# FPGA_System_Monitor.net
KiCad netlist of a schematic drawn in Altium Designer
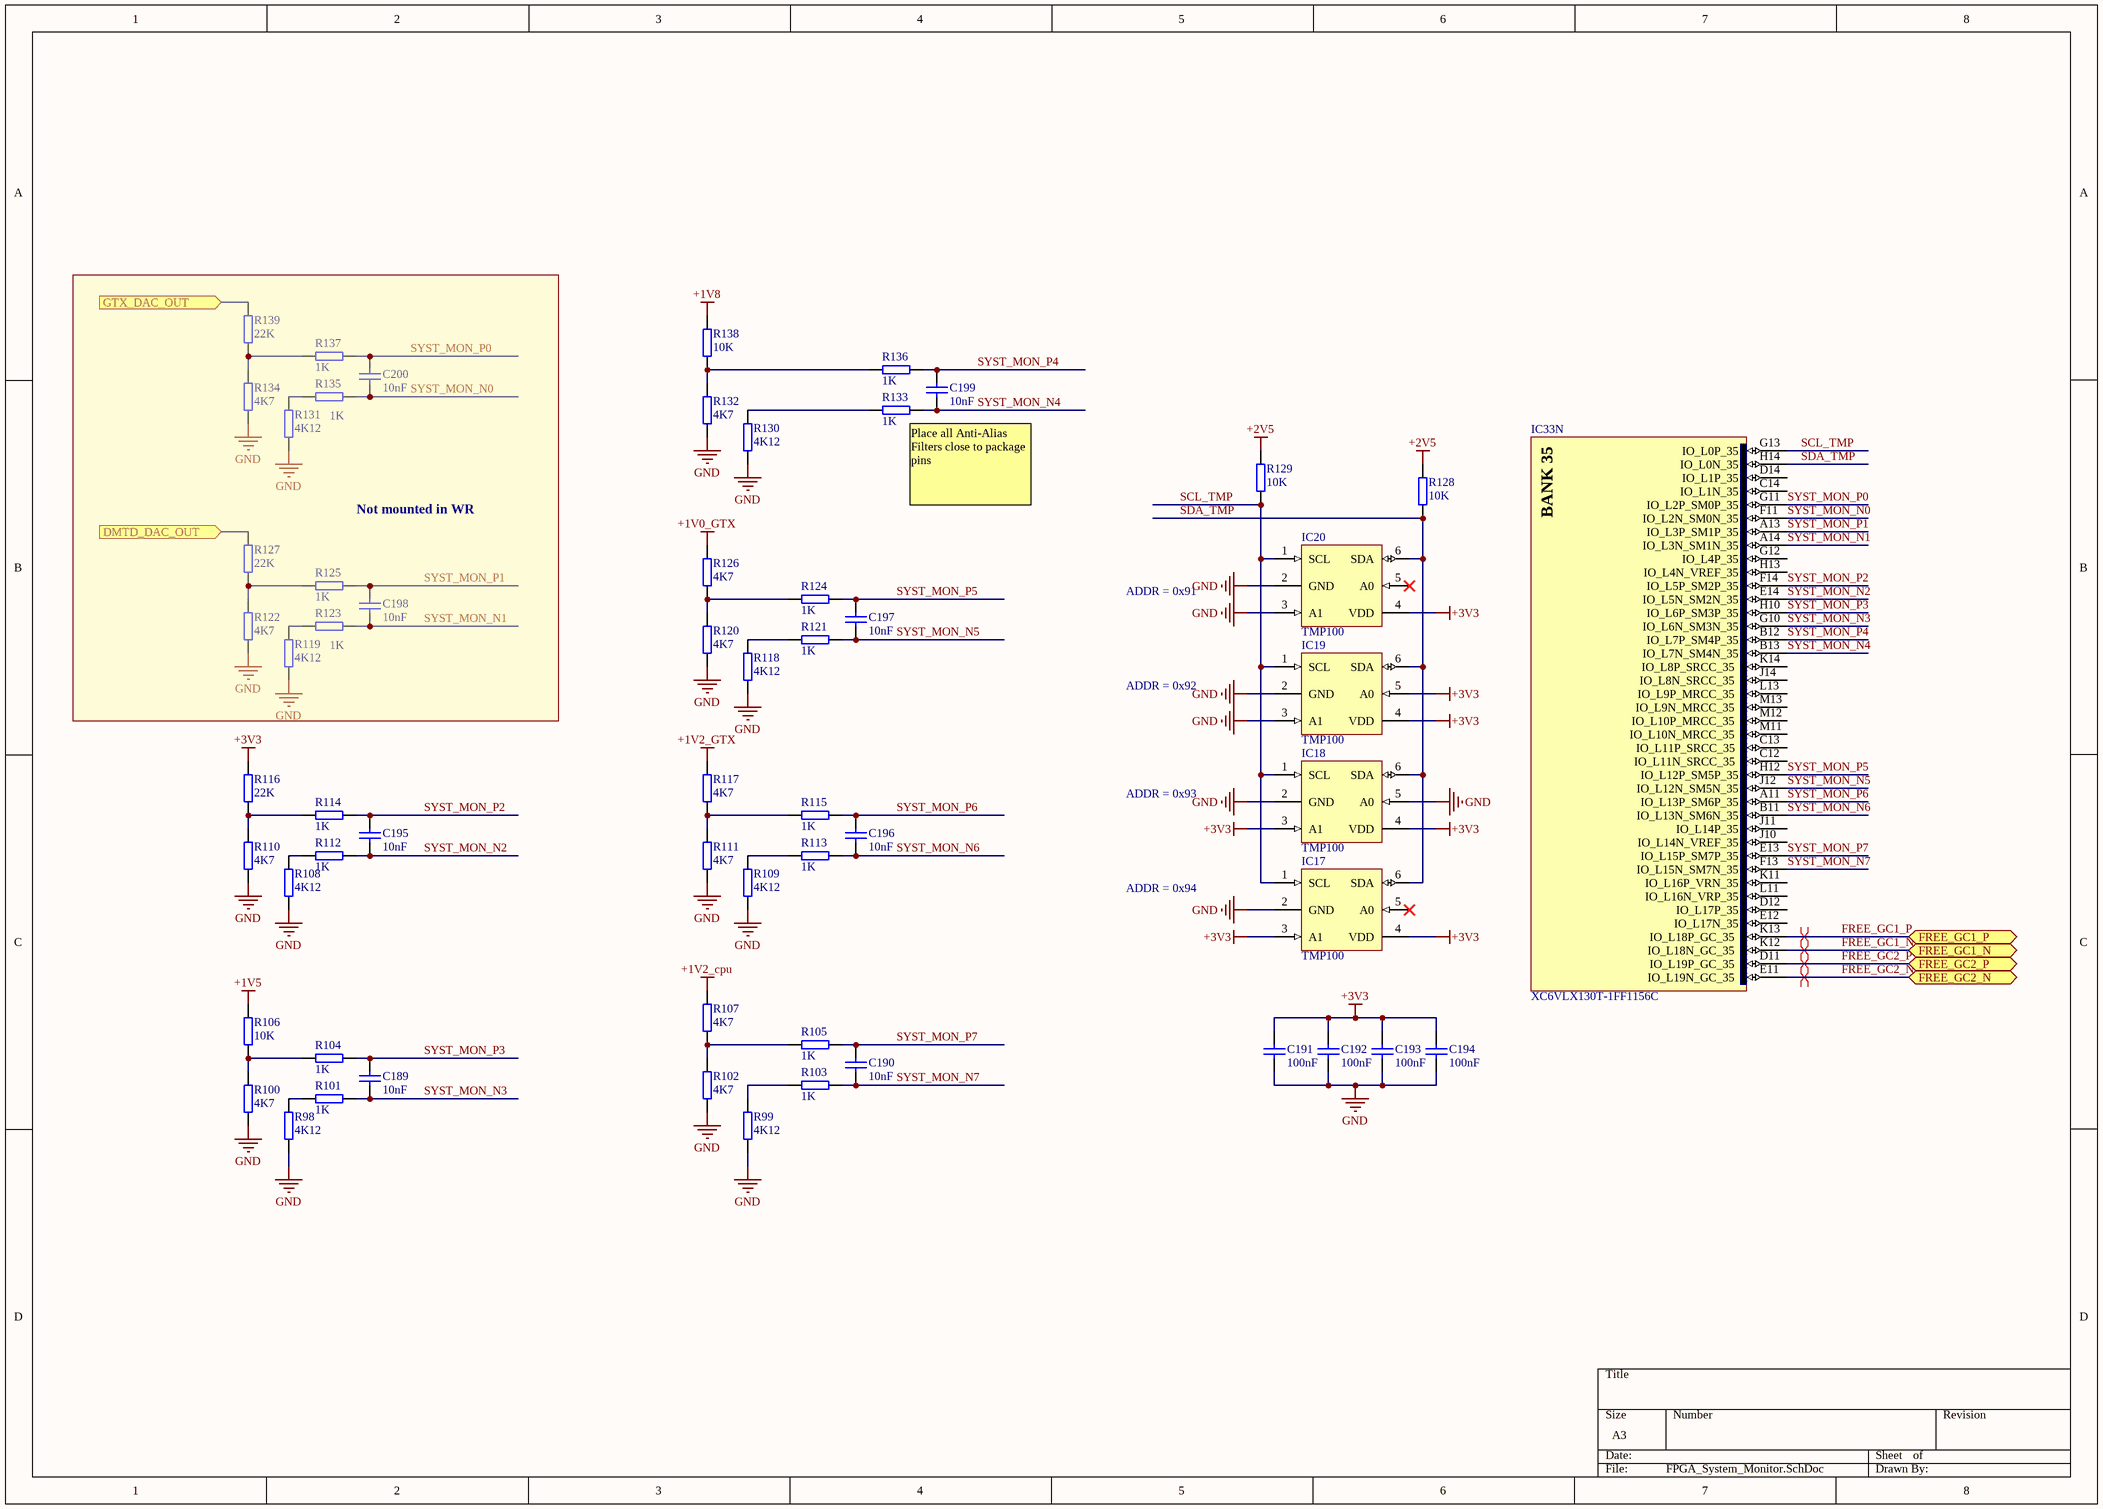
[diagram p0: FPGA_System_Monitor.SchDoc]

(export (version "E")
  (design (tool "Eeschema 10.0.6"))
  (components
    (comp (ref "C189")
      (value "10nF")
      (footprint "CC1005-0402")
      (description "Capacitor")
      (fields
        (field (name "TOLERANCE") "±10%")
        (field (name "VOLTAGE") "25V")
        (field (name "PUBLISHER") "Altium Limited")
      )
      (libsource (lib "wr_switch") (part "Cap"))
    )
    (comp (ref "C190")
      (value "10nF")
      (footprint "CC1005-0402")
      (description "Capacitor")
      (fields
        (field (name "TOLERANCE") "±10%")
        (field (name "VOLTAGE") "25V")
        (field (name "PUBLISHER") "Altium Limited")
      )
      (libsource (lib "wr_switch") (part "Cap"))
    )
    (comp (ref "C191")
      (value "100nF")
      (footprint "CC1005-0402")
      (description "Capacitor")
      (fields
        (field (name "TOLERANCE") "±10%")
        (field (name "VOLTAGE") "16V")
        (field (name "PUBLISHER") "Altium Limited")
      )
      (libsource (lib "wr_switch") (part "Cap"))
    )
    (comp (ref "C192")
      (value "100nF")
      (footprint "CC1005-0402")
      (description "Capacitor")
      (fields
        (field (name "TOLERANCE") "±10%")
        (field (name "VOLTAGE") "16V")
        (field (name "PUBLISHER") "Altium Limited")
      )
      (libsource (lib "wr_switch") (part "Cap"))
    )
    (comp (ref "C193")
      (value "100nF")
      (footprint "CC1005-0402")
      (description "Capacitor")
      (fields
        (field (name "TOLERANCE") "±10%")
        (field (name "VOLTAGE") "16V")
        (field (name "PUBLISHER") "Altium Limited")
      )
      (libsource (lib "wr_switch") (part "Cap"))
    )
    (comp (ref "C194")
      (value "100nF")
      (footprint "CC1005-0402")
      (description "Capacitor")
      (fields
        (field (name "TOLERANCE") "±10%")
        (field (name "VOLTAGE") "16V")
        (field (name "PUBLISHER") "Altium Limited")
      )
      (libsource (lib "wr_switch") (part "Cap"))
    )
    (comp (ref "C195")
      (value "10nF")
      (footprint "CC1005-0402")
      (description "Capacitor")
      (fields
        (field (name "TOLERANCE") "±10%")
        (field (name "VOLTAGE") "25V")
        (field (name "PUBLISHER") "Altium Limited")
      )
      (libsource (lib "wr_switch") (part "Cap"))
    )
    (comp (ref "C196")
      (value "10nF")
      (footprint "CC1005-0402")
      (description "Capacitor")
      (fields
        (field (name "TOLERANCE") "±10%")
        (field (name "VOLTAGE") "25V")
        (field (name "PUBLISHER") "Altium Limited")
      )
      (libsource (lib "wr_switch") (part "Cap"))
    )
    (comp (ref "C197")
      (value "10nF")
      (footprint "CC1005-0402")
      (description "Capacitor")
      (fields
        (field (name "TOLERANCE") "±10%")
        (field (name "VOLTAGE") "25V")
        (field (name "PUBLISHER") "Altium Limited")
      )
      (libsource (lib "wr_switch") (part "Cap"))
    )
    (comp (ref "C198")
      (value "10nF")
      (footprint "CC1005-0402")
      (description "Capacitor")
      (fields
        (field (name "TOLERANCE") "±10%")
        (field (name "VOLTAGE") "25V")
        (field (name "PUBLISHER") "Altium Limited")
      )
      (libsource (lib "wr_switch") (part "Cap"))
    )
    (comp (ref "C199")
      (value "10nF")
      (footprint "CC1005-0402")
      (description "Capacitor")
      (fields
        (field (name "TOLERANCE") "±10%")
        (field (name "VOLTAGE") "25V")
        (field (name "PUBLISHER") "Altium Limited")
      )
      (libsource (lib "wr_switch") (part "Cap"))
    )
    (comp (ref "C200")
      (value "10nF")
      (footprint "CC1005-0402")
      (description "Capacitor")
      (fields
        (field (name "TOLERANCE") "±10%")
        (field (name "VOLTAGE") "25V")
        (field (name "PUBLISHER") "Altium Limited")
      )
      (libsource (lib "wr_switch") (part "Cap"))
    )
    (comp (ref "IC17")
      (value "TMP100")
      (footprint "SOT23A-6L")
      (description "I2C temp. sensor")
      (libsource (lib "wr_switch") (part "TMP100"))
    )
    (comp (ref "IC18")
      (value "TMP100")
      (footprint "SOT23A-6L")
      (description "I2C temp. sensor")
      (libsource (lib "wr_switch") (part "TMP100"))
    )
    (comp (ref "IC19")
      (value "TMP100")
      (footprint "SOT23A-6L")
      (description "I2C temp. sensor")
      (libsource (lib "wr_switch") (part "TMP100"))
    )
    (comp (ref "IC20")
      (value "TMP100")
      (footprint "SOT23A-6L")
      (description "I2C temp. sensor")
      (libsource (lib "wr_switch") (part "TMP100"))
    )
    (comp (ref "IC33")
      (value "XC6VLX130T-1FF1156C")
      (footprint "FF1156")
      (fields (field (name "PUBLISHER") "Altium Limited"))
      (libsource (lib "Xilinx Virtex-6") (part "XC6VLX130T-1FF1156C"))
    )
    (comp (ref "R98")
      (value "4K12")
      (footprint "0402")
      (description "SMD Resistor")
      (fields (field (name "TOLERANCE") "±1%"))
      (libsource (lib "wr_switch") (part "RES_SMD"))
    )
    (comp (ref "R99")
      (value "4K12")
      (footprint "0402")
      (description "SMD Resistor")
      (fields (field (name "TOLERANCE") "±1%"))
      (libsource (lib "wr_switch") (part "RES_SMD"))
    )
    (comp (ref "R100")
      (value "4K7")
      (footprint "0402")
      (description "SMD Resistor")
      (fields (field (name "TOLERANCE") "±1%"))
      (libsource (lib "wr_switch") (part "RES_SMD"))
    )
    (comp (ref "R101")
      (value "1K")
      (footprint "0402")
      (description "SMD Resistor")
      (fields (field (name "TOLERANCE") "±1%"))
      (libsource (lib "wr_switch") (part "RES_SMD"))
    )
    (comp (ref "R102")
      (value "4K7")
      (footprint "0402")
      (description "SMD Resistor")
      (fields (field (name "TOLERANCE") "±1%"))
      (libsource (lib "wr_switch") (part "RES_SMD"))
    )
    (comp (ref "R103")
      (value "1K")
      (footprint "0402")
      (description "SMD Resistor")
      (fields (field (name "TOLERANCE") "±1%"))
      (libsource (lib "wr_switch") (part "RES_SMD"))
    )
    (comp (ref "R104")
      (value "1K")
      (footprint "0402")
      (description "SMD Resistor")
      (fields (field (name "TOLERANCE") "±1%"))
      (libsource (lib "wr_switch") (part "RES_SMD"))
    )
    (comp (ref "R105")
      (value "1K")
      (footprint "0402")
      (description "SMD Resistor")
      (fields (field (name "TOLERANCE") "±1%"))
      (libsource (lib "wr_switch") (part "RES_SMD"))
    )
    (comp (ref "R106")
      (value "10K")
      (footprint "0402")
      (description "SMD Resistor")
      (fields (field (name "TOLERANCE") "±1%") (field (name "Comment") "10k"))
      (libsource (lib "wr_switch") (part "RES_SMD"))
    )
    (comp (ref "R107")
      (value "4K7")
      (footprint "0402")
      (description "SMD Resistor")
      (fields (field (name "TOLERANCE") "±1%"))
      (libsource (lib "wr_switch") (part "RES_SMD"))
    )
    (comp (ref "R108")
      (value "4K12")
      (footprint "0402")
      (description "SMD Resistor")
      (fields (field (name "TOLERANCE") "±1%"))
      (libsource (lib "wr_switch") (part "RES_SMD"))
    )
    (comp (ref "R109")
      (value "4K12")
      (footprint "0402")
      (description "SMD Resistor")
      (fields (field (name "TOLERANCE") "±1%"))
      (libsource (lib "wr_switch") (part "RES_SMD"))
    )
    (comp (ref "R110")
      (value "4K7")
      (footprint "0402")
      (description "SMD Resistor")
      (fields (field (name "TOLERANCE") "±1%"))
      (libsource (lib "wr_switch") (part "RES_SMD"))
    )
    (comp (ref "R111")
      (value "4K7")
      (footprint "0402")
      (description "SMD Resistor")
      (fields (field (name "TOLERANCE") "±1%"))
      (libsource (lib "wr_switch") (part "RES_SMD"))
    )
    (comp (ref "R112")
      (value "1K")
      (footprint "0402")
      (description "SMD Resistor")
      (fields (field (name "TOLERANCE") "±1%"))
      (libsource (lib "wr_switch") (part "RES_SMD"))
    )
    (comp (ref "R113")
      (value "1K")
      (footprint "0402")
      (description "SMD Resistor")
      (fields (field (name "TOLERANCE") "±1%"))
      (libsource (lib "wr_switch") (part "RES_SMD"))
    )
    (comp (ref "R114")
      (value "1K")
      (footprint "0402")
      (description "SMD Resistor")
      (fields (field (name "TOLERANCE") "±1%"))
      (libsource (lib "wr_switch") (part "RES_SMD"))
    )
    (comp (ref "R115")
      (value "1K")
      (footprint "0402")
      (description "SMD Resistor")
      (fields (field (name "TOLERANCE") "±1%"))
      (libsource (lib "wr_switch") (part "RES_SMD"))
    )
    (comp (ref "R116")
      (value "22K")
      (footprint "0402")
      (description "SMD Resistor")
      (fields (field (name "TOLERANCE") "±1%"))
      (libsource (lib "wr_switch") (part "RES_SMD"))
    )
    (comp (ref "R117")
      (value "4K7")
      (footprint "0402")
      (description "SMD Resistor")
      (fields (field (name "TOLERANCE") "±1%"))
      (libsource (lib "wr_switch") (part "RES_SMD"))
    )
    (comp (ref "R118")
      (value "4K12")
      (footprint "0402")
      (description "SMD Resistor")
      (fields (field (name "TOLERANCE") "±1%"))
      (libsource (lib "wr_switch") (part "RES_SMD"))
    )
    (comp (ref "R119")
      (value "4K12")
      (footprint "0402")
      (description "SMD Resistor")
      (fields (field (name "TOLERANCE") "±1%"))
      (libsource (lib "wr_switch") (part "RES_SMD"))
    )
    (comp (ref "R120")
      (value "4K7")
      (footprint "0402")
      (description "SMD Resistor")
      (fields (field (name "TOLERANCE") "±1%"))
      (libsource (lib "wr_switch") (part "RES_SMD"))
    )
    (comp (ref "R121")
      (value "1K")
      (footprint "0402")
      (description "SMD Resistor")
      (fields (field (name "TOLERANCE") "±1%"))
      (libsource (lib "wr_switch") (part "RES_SMD"))
    )
    (comp (ref "R122")
      (value "4K7")
      (footprint "0402")
      (description "SMD Resistor")
      (fields (field (name "TOLERANCE") "±1%"))
      (libsource (lib "wr_switch") (part "RES_SMD"))
    )
    (comp (ref "R123")
      (value "1K")
      (footprint "0402")
      (description "SMD Resistor")
      (fields (field (name "TOLERANCE") "±1%"))
      (libsource (lib "wr_switch") (part "RES_SMD"))
    )
    (comp (ref "R124")
      (value "1K")
      (footprint "0402")
      (description "SMD Resistor")
      (fields (field (name "TOLERANCE") "±1%"))
      (libsource (lib "wr_switch") (part "RES_SMD"))
    )
    (comp (ref "R125")
      (value "1K")
      (footprint "0402")
      (description "SMD Resistor")
      (fields (field (name "TOLERANCE") "±1%"))
      (libsource (lib "wr_switch") (part "RES_SMD"))
    )
    (comp (ref "R126")
      (value "4K7")
      (footprint "0402")
      (description "SMD Resistor")
      (fields (field (name "TOLERANCE") "±1%"))
      (libsource (lib "wr_switch") (part "RES_SMD"))
    )
    (comp (ref "R127")
      (value "22K")
      (footprint "0402")
      (description "SMD Resistor")
      (fields (field (name "TOLERANCE") "±1%"))
      (libsource (lib "wr_switch") (part "RES_SMD"))
    )
    (comp (ref "R128")
      (value "10K")
      (footprint "0402")
      (description "SMD Resistor")
      (fields (field (name "TOLERANCE") "±1%") (field (name "Comment") "10k"))
      (libsource (lib "wr_switch") (part "RES_SMD"))
    )
    (comp (ref "R129")
      (value "10K")
      (footprint "0402")
      (description "SMD Resistor")
      (fields (field (name "TOLERANCE") "±1%") (field (name "Comment") "10k"))
      (libsource (lib "wr_switch") (part "RES_SMD"))
    )
    (comp (ref "R130")
      (value "4K12")
      (footprint "0402")
      (description "SMD Resistor")
      (fields (field (name "TOLERANCE") "±1%"))
      (libsource (lib "wr_switch") (part "RES_SMD"))
    )
    (comp (ref "R131")
      (value "4K12")
      (footprint "0402")
      (description "SMD Resistor")
      (fields (field (name "TOLERANCE") "±1%"))
      (libsource (lib "wr_switch") (part "RES_SMD"))
    )
    (comp (ref "R132")
      (value "4K7")
      (footprint "0402")
      (description "SMD Resistor")
      (fields (field (name "TOLERANCE") "±1%"))
      (libsource (lib "wr_switch") (part "RES_SMD"))
    )
    (comp (ref "R133")
      (value "1K")
      (footprint "0402")
      (description "SMD Resistor")
      (fields (field (name "TOLERANCE") "±1%"))
      (libsource (lib "wr_switch") (part "RES_SMD"))
    )
    (comp (ref "R134")
      (value "4K7")
      (footprint "0402")
      (description "SMD Resistor")
      (fields (field (name "TOLERANCE") "±1%"))
      (libsource (lib "wr_switch") (part "RES_SMD"))
    )
    (comp (ref "R135")
      (value "1K")
      (footprint "0402")
      (description "SMD Resistor")
      (fields (field (name "TOLERANCE") "±1%"))
      (libsource (lib "wr_switch") (part "RES_SMD"))
    )
    (comp (ref "R136")
      (value "1K")
      (footprint "0402")
      (description "SMD Resistor")
      (fields (field (name "TOLERANCE") "±1%"))
      (libsource (lib "wr_switch") (part "RES_SMD"))
    )
    (comp (ref "R137")
      (value "1K")
      (footprint "0402")
      (description "SMD Resistor")
      (fields (field (name "TOLERANCE") "±1%"))
      (libsource (lib "wr_switch") (part "RES_SMD"))
    )
    (comp (ref "R138")
      (value "10K")
      (footprint "0402")
      (description "SMD Resistor")
      (fields (field (name "TOLERANCE") "±1%") (field (name "Comment") "10k"))
      (libsource (lib "wr_switch") (part "RES_SMD"))
    )
    (comp (ref "R139")
      (value "22K")
      (footprint "0402")
      (description "SMD Resistor")
      (fields (field (name "TOLERANCE") "±1%"))
      (libsource (lib "wr_switch") (part "RES_SMD"))
    )
  )
  (nets
    (net (code "1") (name "+1V0_GTX") (class "Default")
      (node (ref "R126") (pin "2") (pinfunction "2_2") (pintype "passive"))
    )
    (net (code "2") (name "+1V2_GTX") (class "Default")
      (node (ref "R117") (pin "2") (pinfunction "2_2") (pintype "passive"))
    )
    (net (code "3") (name "+1V2_cpu") (class "Default")
      (node (ref "R107") (pin "2") (pinfunction "2_2") (pintype "passive"))
    )
    (net (code "4") (name "+1V5") (class "Default")
      (node (ref "R106") (pin "2") (pinfunction "2_2") (pintype "passive"))
    )
    (net (code "5") (name "+1V8") (class "Default")
      (node (ref "R138") (pin "2") (pinfunction "2_2") (pintype "passive"))
    )
    (net (code "6") (name "+2V5") (class "Default")
      (node (ref "R128") (pin "2") (pinfunction "2_2") (pintype "passive"))
      (node (ref "R129") (pin "2") (pinfunction "2_2") (pintype "passive"))
    )
    (net (code "7") (name "+3V3") (class "Default")
      (node (ref "C191") (pin "1") (pinfunction "1_1") (pintype "passive"))
      (node (ref "C192") (pin "1") (pinfunction "1_1") (pintype "passive"))
      (node (ref "C193") (pin "1") (pinfunction "1_1") (pintype "passive"))
      (node (ref "C194") (pin "1") (pinfunction "1_1") (pintype "passive"))
      (node (ref "IC17") (pin "3") (pinfunction "A1_3") (pintype "input"))
      (node (ref "IC17") (pin "4") (pinfunction "VDD_4") (pintype "power_in"))
      (node (ref "IC18") (pin "3") (pinfunction "A1_3") (pintype "input"))
      (node (ref "IC18") (pin "4") (pinfunction "VDD_4") (pintype "power_in"))
      (node (ref "IC19") (pin "4") (pinfunction "VDD_4") (pintype "power_in"))
      (node (ref "IC19") (pin "5") (pinfunction "A0_5") (pintype "input"))
      (node (ref "IC20") (pin "4") (pinfunction "VDD_4") (pintype "power_in"))
      (node (ref "R116") (pin "2") (pinfunction "2_2") (pintype "passive"))
    )
    (net (code "8") (name "/DMTD_DAC_OUT") (class "Default")
      (node (ref "R127") (pin "2") (pinfunction "2_2") (pintype "passive"))
    )
    (net (code "9") (name "/FREE_GC1_N") (class "Default")
      (node (ref "IC33") (pin "K12") (pinfunction "IO_L18N_GC_35_K12") (pintype "bidirectional"))
    )
    (net (code "10") (name "/FREE_GC1_P") (class "Default")
      (node (ref "IC33") (pin "K13") (pinfunction "IO_L18P_GC_35_K13") (pintype "bidirectional"))
    )
    (net (code "11") (name "/FREE_GC2_N") (class "Default")
      (node (ref "IC33") (pin "E11") (pinfunction "IO_L19N_GC_35_E11") (pintype "bidirectional"))
    )
    (net (code "12") (name "/FREE_GC2_P") (class "Default")
      (node (ref "IC33") (pin "D11") (pinfunction "IO_L19P_GC_35_D11") (pintype "bidirectional"))
    )
    (net (code "13") (name "/GTX_DAC_OUT") (class "Default")
      (node (ref "R139") (pin "2") (pinfunction "2_2") (pintype "passive"))
    )
    (net (code "14") (name "/SCL_TMP") (class "Default")
      (node (ref "IC17") (pin "1") (pinfunction "SCL_1") (pintype "input"))
      (node (ref "IC18") (pin "1") (pinfunction "SCL_1") (pintype "input"))
      (node (ref "IC19") (pin "1") (pinfunction "SCL_1") (pintype "input"))
      (node (ref "IC20") (pin "1") (pinfunction "SCL_1") (pintype "input"))
      (node (ref "IC33") (pin "G13") (pinfunction "IO_L0P_35_G13") (pintype "bidirectional"))
      (node (ref "R129") (pin "1") (pinfunction "1_1") (pintype "passive"))
    )
    (net (code "15") (name "/SDA_TMP") (class "Default")
      (node (ref "IC17") (pin "6") (pinfunction "SDA_6") (pintype "bidirectional"))
      (node (ref "IC18") (pin "6") (pinfunction "SDA_6") (pintype "bidirectional"))
      (node (ref "IC19") (pin "6") (pinfunction "SDA_6") (pintype "bidirectional"))
      (node (ref "IC20") (pin "6") (pinfunction "SDA_6") (pintype "bidirectional"))
      (node (ref "IC33") (pin "H14") (pinfunction "IO_L0N_35_H14") (pintype "bidirectional"))
      (node (ref "R128") (pin "1") (pinfunction "1_1") (pintype "passive"))
    )
    (net (code "16") (name "/SYST_MON_N0") (class "Default")
      (node (ref "C200") (pin "1") (pinfunction "1_1") (pintype "passive"))
      (node (ref "IC33") (pin "F11") (pinfunction "IO_L2N_SM0N_35_F11") (pintype "bidirectional"))
      (node (ref "R135") (pin "1") (pinfunction "1_1") (pintype "passive"))
    )
    (net (code "17") (name "/SYST_MON_N1") (class "Default")
      (node (ref "C198") (pin "1") (pinfunction "1_1") (pintype "passive"))
      (node (ref "IC33") (pin "A14") (pinfunction "IO_L3N_SM1N_35_A14") (pintype "bidirectional"))
      (node (ref "R123") (pin "1") (pinfunction "1_1") (pintype "passive"))
    )
    (net (code "18") (name "/SYST_MON_N2") (class "Default")
      (node (ref "C195") (pin "1") (pinfunction "1_1") (pintype "passive"))
      (node (ref "IC33") (pin "E14") (pinfunction "IO_L5N_SM2N_35_E14") (pintype "bidirectional"))
      (node (ref "R112") (pin "1") (pinfunction "1_1") (pintype "passive"))
    )
    (net (code "19") (name "/SYST_MON_N3") (class "Default")
      (node (ref "C189") (pin "1") (pinfunction "1_1") (pintype "passive"))
      (node (ref "IC33") (pin "G10") (pinfunction "IO_L6N_SM3N_35_G10") (pintype "bidirectional"))
      (node (ref "R101") (pin "1") (pinfunction "1_1") (pintype "passive"))
    )
    (net (code "20") (name "/SYST_MON_N4") (class "Default")
      (node (ref "C199") (pin "1") (pinfunction "1_1") (pintype "passive"))
      (node (ref "IC33") (pin "B13") (pinfunction "IO_L7N_SM4N_35_B13") (pintype "bidirectional"))
      (node (ref "R133") (pin "1") (pinfunction "1_1") (pintype "passive"))
    )
    (net (code "21") (name "/SYST_MON_N5") (class "Default")
      (node (ref "C197") (pin "1") (pinfunction "1_1") (pintype "passive"))
      (node (ref "IC33") (pin "J12") (pinfunction "IO_L12N_SM5N_35_J12") (pintype "bidirectional"))
      (node (ref "R121") (pin "1") (pinfunction "1_1") (pintype "passive"))
    )
    (net (code "22") (name "/SYST_MON_N6") (class "Default")
      (node (ref "C196") (pin "1") (pinfunction "1_1") (pintype "passive"))
      (node (ref "IC33") (pin "B11") (pinfunction "IO_L13N_SM6N_35_B11") (pintype "bidirectional"))
      (node (ref "R113") (pin "1") (pinfunction "1_1") (pintype "passive"))
    )
    (net (code "23") (name "/SYST_MON_N7") (class "Default")
      (node (ref "C190") (pin "1") (pinfunction "1_1") (pintype "passive"))
      (node (ref "IC33") (pin "F13") (pinfunction "IO_L15N_SM7N_35_F13") (pintype "bidirectional"))
      (node (ref "R103") (pin "1") (pinfunction "1_1") (pintype "passive"))
    )
    (net (code "24") (name "/SYST_MON_P0") (class "Default")
      (node (ref "C200") (pin "2") (pinfunction "2_2") (pintype "passive"))
      (node (ref "IC33") (pin "G11") (pinfunction "IO_L2P_SM0P_35_G11") (pintype "bidirectional"))
      (node (ref "R137") (pin "1") (pinfunction "1_1") (pintype "passive"))
    )
    (net (code "25") (name "/SYST_MON_P1") (class "Default")
      (node (ref "C198") (pin "2") (pinfunction "2_2") (pintype "passive"))
      (node (ref "IC33") (pin "A13") (pinfunction "IO_L3P_SM1P_35_A13") (pintype "bidirectional"))
      (node (ref "R125") (pin "1") (pinfunction "1_1") (pintype "passive"))
    )
    (net (code "26") (name "/SYST_MON_P2") (class "Default")
      (node (ref "C195") (pin "2") (pinfunction "2_2") (pintype "passive"))
      (node (ref "IC33") (pin "F14") (pinfunction "IO_L5P_SM2P_35_F14") (pintype "bidirectional"))
      (node (ref "R114") (pin "1") (pinfunction "1_1") (pintype "passive"))
    )
    (net (code "27") (name "/SYST_MON_P3") (class "Default")
      (node (ref "C189") (pin "2") (pinfunction "2_2") (pintype "passive"))
      (node (ref "IC33") (pin "H10") (pinfunction "IO_L6P_SM3P_35_H10") (pintype "bidirectional"))
      (node (ref "R104") (pin "1") (pinfunction "1_1") (pintype "passive"))
    )
    (net (code "28") (name "/SYST_MON_P4") (class "Default")
      (node (ref "C199") (pin "2") (pinfunction "2_2") (pintype "passive"))
      (node (ref "IC33") (pin "B12") (pinfunction "IO_L7P_SM4P_35_B12") (pintype "bidirectional"))
      (node (ref "R136") (pin "1") (pinfunction "1_1") (pintype "passive"))
    )
    (net (code "29") (name "/SYST_MON_P5") (class "Default")
      (node (ref "C197") (pin "2") (pinfunction "2_2") (pintype "passive"))
      (node (ref "IC33") (pin "H12") (pinfunction "IO_L12P_SM5P_35_H12") (pintype "bidirectional"))
      (node (ref "R124") (pin "1") (pinfunction "1_1") (pintype "passive"))
    )
    (net (code "30") (name "/SYST_MON_P6") (class "Default")
      (node (ref "C196") (pin "2") (pinfunction "2_2") (pintype "passive"))
      (node (ref "IC33") (pin "A11") (pinfunction "IO_L13P_SM6P_35_A11") (pintype "bidirectional"))
      (node (ref "R115") (pin "1") (pinfunction "1_1") (pintype "passive"))
    )
    (net (code "31") (name "/SYST_MON_P7") (class "Default")
      (node (ref "C190") (pin "2") (pinfunction "2_2") (pintype "passive"))
      (node (ref "IC33") (pin "E13") (pinfunction "IO_L15P_SM7P_35_E13") (pintype "bidirectional"))
      (node (ref "R105") (pin "1") (pinfunction "1_1") (pintype "passive"))
    )
    (net (code "32") (name "GND") (class "Default")
      (node (ref "C191") (pin "2") (pinfunction "2_2") (pintype "passive"))
      (node (ref "C192") (pin "2") (pinfunction "2_2") (pintype "passive"))
      (node (ref "C193") (pin "2") (pinfunction "2_2") (pintype "passive"))
      (node (ref "C194") (pin "2") (pinfunction "2_2") (pintype "passive"))
      (node (ref "IC17") (pin "2") (pinfunction "GND_2") (pintype "power_in"))
      (node (ref "IC18") (pin "2") (pinfunction "GND_2") (pintype "power_in"))
      (node (ref "IC18") (pin "5") (pinfunction "A0_5") (pintype "input"))
      (node (ref "IC19") (pin "2") (pinfunction "GND_2") (pintype "power_in"))
      (node (ref "IC19") (pin "3") (pinfunction "A1_3") (pintype "input"))
      (node (ref "IC20") (pin "2") (pinfunction "GND_2") (pintype "power_in"))
      (node (ref "IC20") (pin "3") (pinfunction "A1_3") (pintype "input"))
      (node (ref "R100") (pin "1") (pinfunction "1_1") (pintype "passive"))
      (node (ref "R102") (pin "1") (pinfunction "1_1") (pintype "passive"))
      (node (ref "R108") (pin "1") (pinfunction "1_1") (pintype "passive"))
      (node (ref "R109") (pin "1") (pinfunction "1_1") (pintype "passive"))
      (node (ref "R110") (pin "1") (pinfunction "1_1") (pintype "passive"))
      (node (ref "R111") (pin "1") (pinfunction "1_1") (pintype "passive"))
      (node (ref "R118") (pin "1") (pinfunction "1_1") (pintype "passive"))
      (node (ref "R119") (pin "1") (pinfunction "1_1") (pintype "passive"))
      (node (ref "R120") (pin "1") (pinfunction "1_1") (pintype "passive"))
      (node (ref "R122") (pin "1") (pinfunction "1_1") (pintype "passive"))
      (node (ref "R130") (pin "1") (pinfunction "1_1") (pintype "passive"))
      (node (ref "R131") (pin "1") (pinfunction "1_1") (pintype "passive"))
      (node (ref "R132") (pin "1") (pinfunction "1_1") (pintype "passive"))
      (node (ref "R134") (pin "1") (pinfunction "1_1") (pintype "passive"))
      (node (ref "R98") (pin "1") (pinfunction "1_1") (pintype "passive"))
      (node (ref "R99") (pin "1") (pinfunction "1_1") (pintype "passive"))
    )
    (net (code "33") (name "Net-(R100-Pad2)") (class "Default")
      (node (ref "R100") (pin "2") (pinfunction "2_2") (pintype "passive"))
      (node (ref "R104") (pin "2") (pinfunction "2_2") (pintype "passive"))
      (node (ref "R106") (pin "1") (pinfunction "1_1") (pintype "passive"))
    )
    (net (code "34") (name "Net-(R101-Pad2)") (class "Default")
      (node (ref "R101") (pin "2") (pinfunction "2_2") (pintype "passive"))
      (node (ref "R98") (pin "2") (pinfunction "2_2") (pintype "passive"))
    )
    (net (code "35") (name "Net-(R102-Pad2)") (class "Default")
      (node (ref "R102") (pin "2") (pinfunction "2_2") (pintype "passive"))
      (node (ref "R105") (pin "2") (pinfunction "2_2") (pintype "passive"))
      (node (ref "R107") (pin "1") (pinfunction "1_1") (pintype "passive"))
    )
    (net (code "36") (name "Net-(R103-Pad2)") (class "Default")
      (node (ref "R103") (pin "2") (pinfunction "2_2") (pintype "passive"))
      (node (ref "R99") (pin "2") (pinfunction "2_2") (pintype "passive"))
    )
    (net (code "37") (name "Net-(R108-Pad2)") (class "Default")
      (node (ref "R108") (pin "2") (pinfunction "2_2") (pintype "passive"))
      (node (ref "R112") (pin "2") (pinfunction "2_2") (pintype "passive"))
    )
    (net (code "38") (name "Net-(R109-Pad2)") (class "Default")
      (node (ref "R109") (pin "2") (pinfunction "2_2") (pintype "passive"))
      (node (ref "R113") (pin "2") (pinfunction "2_2") (pintype "passive"))
    )
    (net (code "39") (name "Net-(R110-Pad2)") (class "Default")
      (node (ref "R110") (pin "2") (pinfunction "2_2") (pintype "passive"))
      (node (ref "R114") (pin "2") (pinfunction "2_2") (pintype "passive"))
      (node (ref "R116") (pin "1") (pinfunction "1_1") (pintype "passive"))
    )
    (net (code "40") (name "Net-(R111-Pad2)") (class "Default")
      (node (ref "R111") (pin "2") (pinfunction "2_2") (pintype "passive"))
      (node (ref "R115") (pin "2") (pinfunction "2_2") (pintype "passive"))
      (node (ref "R117") (pin "1") (pinfunction "1_1") (pintype "passive"))
    )
    (net (code "41") (name "Net-(R118-Pad2)") (class "Default")
      (node (ref "R118") (pin "2") (pinfunction "2_2") (pintype "passive"))
      (node (ref "R121") (pin "2") (pinfunction "2_2") (pintype "passive"))
    )
    (net (code "42") (name "Net-(R119-Pad2)") (class "Default")
      (node (ref "R119") (pin "2") (pinfunction "2_2") (pintype "passive"))
      (node (ref "R123") (pin "2") (pinfunction "2_2") (pintype "passive"))
    )
    (net (code "43") (name "Net-(R120-Pad2)") (class "Default")
      (node (ref "R120") (pin "2") (pinfunction "2_2") (pintype "passive"))
      (node (ref "R124") (pin "2") (pinfunction "2_2") (pintype "passive"))
      (node (ref "R126") (pin "1") (pinfunction "1_1") (pintype "passive"))
    )
    (net (code "44") (name "Net-(R122-Pad2)") (class "Default")
      (node (ref "R122") (pin "2") (pinfunction "2_2") (pintype "passive"))
      (node (ref "R125") (pin "2") (pinfunction "2_2") (pintype "passive"))
      (node (ref "R127") (pin "1") (pinfunction "1_1") (pintype "passive"))
    )
    (net (code "45") (name "Net-(R130-Pad2)") (class "Default")
      (node (ref "R130") (pin "2") (pinfunction "2_2") (pintype "passive"))
      (node (ref "R133") (pin "2") (pinfunction "2_2") (pintype "passive"))
    )
    (net (code "46") (name "Net-(R131-Pad2)") (class "Default")
      (node (ref "R131") (pin "2") (pinfunction "2_2") (pintype "passive"))
      (node (ref "R135") (pin "2") (pinfunction "2_2") (pintype "passive"))
    )
    (net (code "47") (name "Net-(R132-Pad2)") (class "Default")
      (node (ref "R132") (pin "2") (pinfunction "2_2") (pintype "passive"))
      (node (ref "R136") (pin "2") (pinfunction "2_2") (pintype "passive"))
      (node (ref "R138") (pin "1") (pinfunction "1_1") (pintype "passive"))
    )
    (net (code "48") (name "Net-(R134-Pad2)") (class "Default")
      (node (ref "R134") (pin "2") (pinfunction "2_2") (pintype "passive"))
      (node (ref "R137") (pin "2") (pinfunction "2_2") (pintype "passive"))
      (node (ref "R139") (pin "1") (pinfunction "1_1") (pintype "passive"))
    )
    (net (code "49") (name "unconnected-(IC17-A0-Pad5)") (class "Default")
      (node (ref "IC17") (pin "5") (pinfunction "A0_5") (pintype "input+no_connect"))
    )
    (net (code "50") (name "unconnected-(IC20-A0-Pad5)") (class "Default")
      (node (ref "IC20") (pin "5") (pinfunction "A0_5") (pintype "input+no_connect"))
    )
    (net (code "51") (name "unconnected-(IC33N-IO_L1N_35-PadC14)") (class "Default")
      (node (ref "IC33") (pin "C14") (pinfunction "IO_L1N_35_C14") (pintype "bidirectional"))
    )
    (net (code "52") (name "unconnected-(IC33N-IO_L1P_35-PadD14)") (class "Default")
      (node (ref "IC33") (pin "D14") (pinfunction "IO_L1P_35_D14") (pintype "bidirectional"))
    )
    (net (code "53") (name "unconnected-(IC33N-IO_L4N_VREF_35-PadH13)") (class "Default")
      (node (ref "IC33") (pin "H13") (pinfunction "IO_L4N_VREF_35_H13") (pintype "bidirectional"))
    )
    (net (code "54") (name "unconnected-(IC33N-IO_L4P_35-PadG12)") (class "Default")
      (node (ref "IC33") (pin "G12") (pinfunction "IO_L4P_35_G12") (pintype "bidirectional"))
    )
    (net (code "55") (name "unconnected-(IC33N-IO_L8N_SRCC_35-PadJ14)") (class "Default")
      (node (ref "IC33") (pin "J14") (pinfunction "IO_L8N_SRCC_35_J14") (pintype "bidirectional"))
    )
    (net (code "56") (name "unconnected-(IC33N-IO_L8P_SRCC_35-PadK14)") (class "Default")
      (node (ref "IC33") (pin "K14") (pinfunction "IO_L8P_SRCC_35_K14") (pintype "bidirectional"))
    )
    (net (code "57") (name "unconnected-(IC33N-IO_L9N_MRCC_35-PadM13)") (class "Default")
      (node (ref "IC33") (pin "M13") (pinfunction "IO_L9N_MRCC_35_M13") (pintype "bidirectional"))
    )
    (net (code "58") (name "unconnected-(IC33N-IO_L9P_MRCC_35-PadL13)") (class "Default")
      (node (ref "IC33") (pin "L13") (pinfunction "IO_L9P_MRCC_35_L13") (pintype "bidirectional"))
    )
    (net (code "59") (name "unconnected-(IC33N-IO_L10N_MRCC_35-PadM11)") (class "Default")
      (node (ref "IC33") (pin "M11") (pinfunction "IO_L10N_MRCC_35_M11") (pintype "bidirectional"))
    )
    (net (code "60") (name "unconnected-(IC33N-IO_L10P_MRCC_35-PadM12)") (class "Default")
      (node (ref "IC33") (pin "M12") (pinfunction "IO_L10P_MRCC_35_M12") (pintype "bidirectional"))
    )
    (net (code "61") (name "unconnected-(IC33N-IO_L11N_SRCC_35-PadC12)") (class "Default")
      (node (ref "IC33") (pin "C12") (pinfunction "IO_L11N_SRCC_35_C12") (pintype "bidirectional"))
    )
    (net (code "62") (name "unconnected-(IC33N-IO_L11P_SRCC_35-PadC13)") (class "Default")
      (node (ref "IC33") (pin "C13") (pinfunction "IO_L11P_SRCC_35_C13") (pintype "bidirectional"))
    )
    (net (code "63") (name "unconnected-(IC33N-IO_L14N_VREF_35-PadJ10)") (class "Default")
      (node (ref "IC33") (pin "J10") (pinfunction "IO_L14N_VREF_35_J10") (pintype "bidirectional"))
    )
    (net (code "64") (name "unconnected-(IC33N-IO_L14P_35-PadJ11)") (class "Default")
      (node (ref "IC33") (pin "J11") (pinfunction "IO_L14P_35_J11") (pintype "bidirectional"))
    )
    (net (code "65") (name "unconnected-(IC33N-IO_L16N_VRP_35-PadL11)") (class "Default")
      (node (ref "IC33") (pin "L11") (pinfunction "IO_L16N_VRP_35_L11") (pintype "bidirectional"))
    )
    (net (code "66") (name "unconnected-(IC33N-IO_L16P_VRN_35-PadK11)") (class "Default")
      (node (ref "IC33") (pin "K11") (pinfunction "IO_L16P_VRN_35_K11") (pintype "bidirectional"))
    )
    (net (code "67") (name "unconnected-(IC33N-IO_L17N_35-PadE12)") (class "Default")
      (node (ref "IC33") (pin "E12") (pinfunction "IO_L17N_35_E12") (pintype "bidirectional"))
    )
    (net (code "68") (name "unconnected-(IC33N-IO_L17P_35-PadD12)") (class "Default")
      (node (ref "IC33") (pin "D12") (pinfunction "IO_L17P_35_D12") (pintype "bidirectional"))
    )
  )
)
